# MACH.net
KiCad netlist of a schematic drawn in Altium Designer
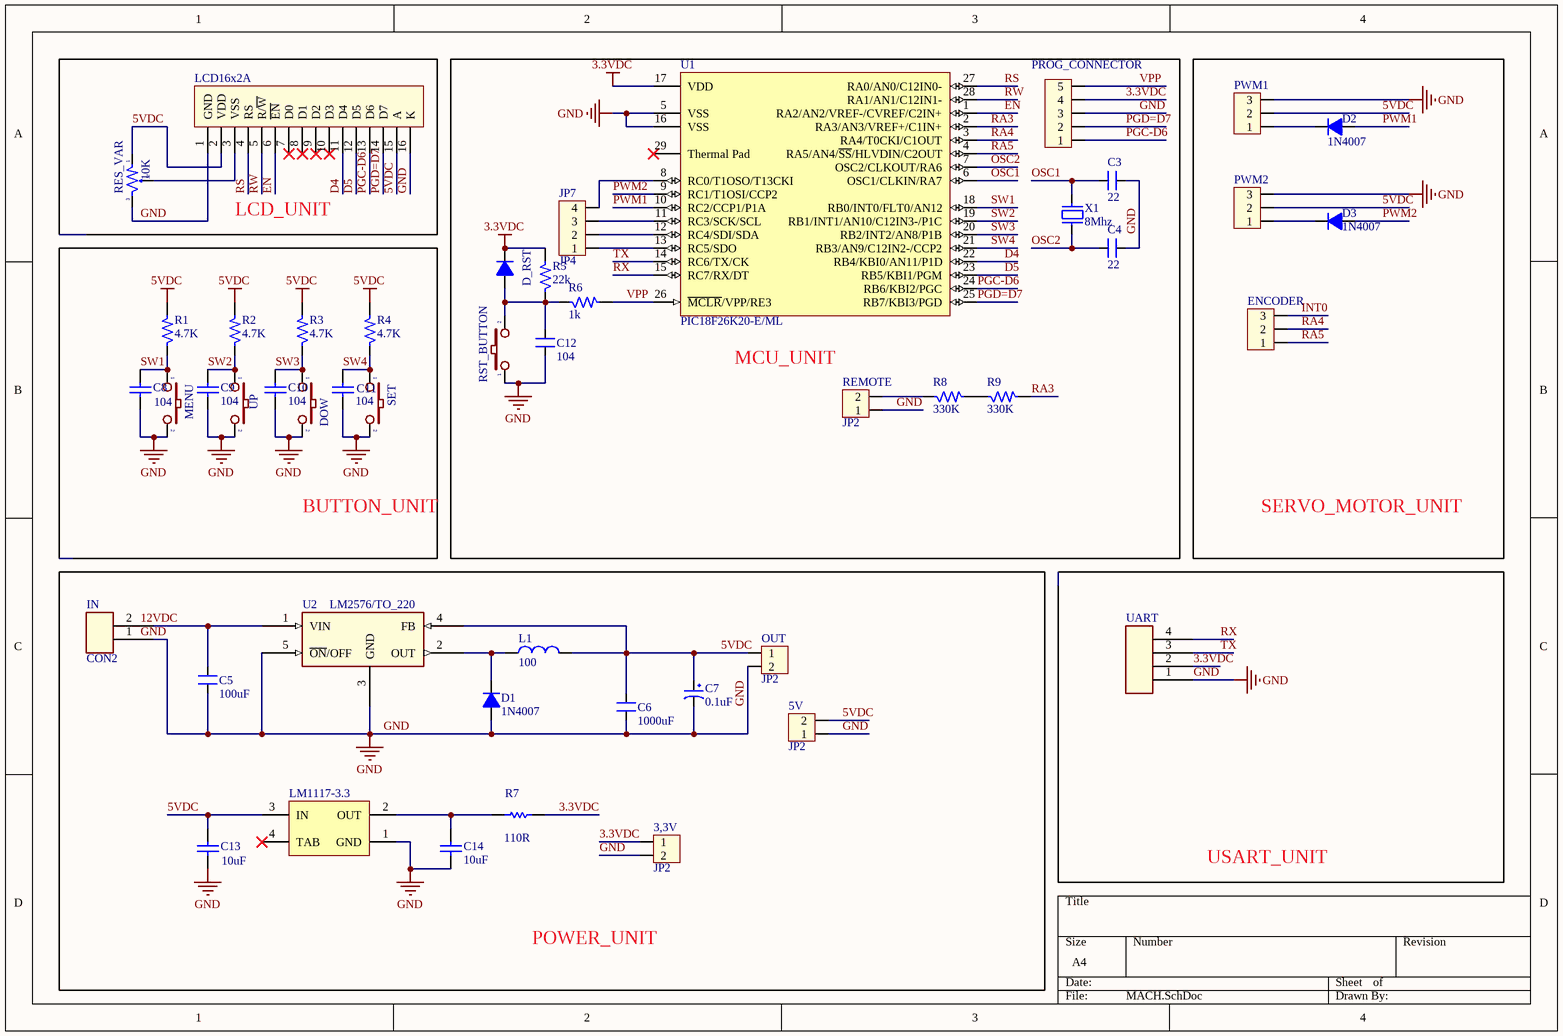
[diagram p0: MACH.SchDoc]

(export (version "E")
  (design (tool "Eeschema 10.0.6"))
  (components
    (comp (ref "3,3V")
      (value "JP2")
      (footprint "syhaunguyen:CON2")
      (description "Connector 2")
      (libsource (lib "") (part "Con2_1"))
    )
    (comp (ref "5V")
      (value "JP2")
      (footprint "syhaunguyen:CON2")
      (description "Connector 2")
      (libsource (lib "syhaunguyen") (part "Con2"))
    )
    (comp (ref "C3")
      (value "22")
      (footprint "SM-0805")
      (description "Cap SMD")
      (libsource (lib "syhaunguyen") (part "CM"))
    )
    (comp (ref "C4")
      (value "22")
      (footprint "SM-0805")
      (description "Cap SMD")
      (libsource (lib "syhaunguyen") (part "CM"))
    )
    (comp (ref "C5")
      (value "100uF")
      (footprint "CP1/2.5_SM")
      (description "Cap SMD")
      (libsource (lib "syhaunguyen") (part "CM"))
    )
    (comp (ref "C6")
      (value "1000uF")
      (footprint "CP2/4")
      (description "Cap SMD")
      (libsource (lib "syhaunguyen") (part "CM"))
    )
    (comp (ref "C7")
      (value "0.1uF")
      (footprint "CP1/2")
      (description "Cap P  0,1uF < 22uF , 16 - 50V")
      (libsource (lib "syhaunguyen") (part "CP1"))
    )
    (comp (ref "C8")
      (value "104")
      (footprint "SM-0805")
      (description "Capacitor")
      (fields (field (name "Comment") "Cap") (field (name "PUBLISHER") "Altium Limited"))
      (libsource (lib "Miscellaneous Devices") (part "Cap"))
    )
    (comp (ref "C9")
      (value "104")
      (footprint "SM-0805")
      (description "Capacitor")
      (fields (field (name "Comment") "Cap") (field (name "PUBLISHER") "Altium Limited"))
      (libsource (lib "Miscellaneous Devices") (part "Cap"))
    )
    (comp (ref "C10")
      (value "104")
      (footprint "SM-0805")
      (description "Capacitor")
      (fields (field (name "Comment") "Cap") (field (name "PUBLISHER") "Altium Limited"))
      (libsource (lib "Miscellaneous Devices") (part "Cap"))
    )
    (comp (ref "C11")
      (value "104")
      (footprint "syhaunguyen:SM-0805")
      (description "Capacitor")
      (fields (field (name "Comment") "Cap") (field (name "PUBLISHER") "Altium Limited"))
      (libsource (lib "Miscellaneous Devices") (part "Cap"))
    )
    (comp (ref "C12")
      (value "104")
      (footprint "SM-0805")
      (description "Cap SMD")
      (libsource (lib "syhaunguyen") (part "CM"))
    )
    (comp (ref "C13")
      (value "10uF")
      (footprint "CP1/2")
      (description "Capacitor")
      (fields (field (name "Comment") "Cap") (field (name "PUBLISHER") "Altium Limited"))
      (libsource (lib "Miscellaneous Devices") (part "Cap"))
    )
    (comp (ref "C14")
      (value "10uF")
      (footprint "CP1/2")
      (description "Capacitor")
      (fields (field (name "Comment") "Cap") (field (name "PUBLISHER") "Altium Limited"))
      (libsource (lib "Miscellaneous Devices") (part "Cap"))
    )
    (comp (ref "D1")
      (value "1N4007")
      (footprint "D2AN")
      (description "Diode 1A")
      (libsource (lib "syhaunguyen") (part "D1A"))
    )
    (comp (ref "D2")
      (value "1N4007")
      (footprint "D2A")
      (description "Diode 1A")
      (libsource (lib "syhaunguyen") (part "D1A"))
    )
    (comp (ref "D3")
      (value "1N4007")
      (footprint "D2A")
      (description "Diode 1A")
      (libsource (lib "syhaunguyen") (part "D1A"))
    )
    (comp (ref "DOW")
      (value "SW")
      (footprint "SW2")
      (description "Switch button 2 pin")
      (libsource (lib "syhaunguyen") (part "SW2"))
    )
    (comp (ref "D_RST")
      (value "1N5408")
      (footprint "D2A")
      (description "Diode 5A")
      (libsource (lib "syhaunguyen") (part "D5A"))
    )
    (comp (ref "ENCODER")
      (value "JP3")
      (footprint "syhaunguyen:CON3")
      (description "Connector 3")
      (libsource (lib "syhaunguyen") (part "Con3"))
    )
    (comp (ref "IN")
      (value "CON2")
      (footprint "syhaunguyen:CON2")
      (libsource (lib "NEWSYS_Library_V3") (part "CON2"))
    )
    (comp (ref "JP7")
      (value "JP4")
      (footprint "syhaunguyen:CON4")
      (description "Connector 4")
      (libsource (lib "syhaunguyen") (part "Con4"))
    )
    (comp (ref "L1")
      (value "100")
      (footprint "L/0.4")
      (description "Inductor")
      (libsource (lib "syhaunguyen") (part "L1"))
    )
    (comp (ref "LCD16x2A")
      (value "LCD")
      (footprint "LCD16X2")
      (description "LCD dipslay 16 char, 2 line")
      (libsource (lib "syhaunguyen") (part "LCD16x2"))
    )
    (comp (ref "LM1117-3.3")
      (value "LM1117MP-1.2")
      (footprint "LM1117-SOP")
      (description "800mA Low-Dropout Linear Regulator")
      (fields
        (field (name "PARTNUMBER") "LM1117MP-2.5")
        (field (name "MANUFACTURER") "National Semiconductor")
        (field (name "PUBLISHER") "Altium Limited")
      )
      (libsource (lib "NSC LDO") (part "LM1117MP-2.5"))
    )
    (comp (ref "MENU")
      (value "SW")
      (footprint "SW2")
      (description "Switch button 2 pin")
      (libsource (lib "syhaunguyen") (part "SW2"))
    )
    (comp (ref "OUT")
      (value "JP2")
      (footprint "syhaunguyen:CON2")
      (description "Connector 2")
      (libsource (lib "") (part "Con2_1"))
    )
    (comp (ref "PROG_CONNECTOR")
      (value "~")
      (footprint "CON5")
      (description "Connector 5")
      (libsource (lib "syhaunguyen") (part "Con5"))
    )
    (comp (ref "PWM1")
      (value "JP3")
      (footprint "CON3")
      (description "Connector 3")
      (libsource (lib "syhaunguyen") (part "Con3"))
    )
    (comp (ref "PWM2")
      (value "JP3")
      (footprint "CON3")
      (description "Connector 3")
      (libsource (lib "syhaunguyen") (part "Con3"))
    )
    (comp (ref "R1")
      (value "4.7K")
      (footprint "SM-0805")
      (description "Resistor 1/4W")
      (libsource (lib "syhaunguyen") (part "R"))
    )
    (comp (ref "R2")
      (value "4.7K")
      (footprint "SM-0805")
      (description "Resistor 1/4W")
      (libsource (lib "syhaunguyen") (part "R"))
    )
    (comp (ref "R3")
      (value "4.7K")
      (footprint "SM-0805")
      (description "Resistor 1/4W")
      (libsource (lib "syhaunguyen") (part "R"))
    )
    (comp (ref "R4")
      (value "4.7K")
      (footprint "SM-0805")
      (description "Resistor 1/4W")
      (libsource (lib "syhaunguyen") (part "R"))
    )
    (comp (ref "R5")
      (value "22k")
      (footprint "SM-0805")
      (description "Resistor 1/4W")
      (libsource (lib "syhaunguyen") (part "R"))
    )
    (comp (ref "R6")
      (value "1k")
      (footprint "SM-0805")
      (description "Resistor 1/4W")
      (libsource (lib "syhaunguyen") (part "R"))
    )
    (comp (ref "R7")
      (value "110R")
      (footprint "SM-0805")
      (description "Resistor")
      (fields (field (name "Comment") "Res1") (field (name "PUBLISHER") "Altium Limited"))
      (libsource (lib "Miscellaneous Devices") (part "Res1"))
    )
    (comp (ref "R8")
      (value "330K")
      (footprint "SM-1206")
      (description "Resistor 1/4W")
      (libsource (lib "syhaunguyen") (part "R"))
    )
    (comp (ref "R9")
      (value "330K")
      (footprint "SM-1206")
      (description "Resistor 1/4W")
      (libsource (lib "syhaunguyen") (part "R"))
    )
    (comp (ref "REMOTE")
      (value "JP2")
      (footprint "syhaunguyen:CON2")
      (description "Connector 2")
      (libsource (lib "syhaunguyen") (part "Con2"))
    )
    (comp (ref "RES_VAR")
      (value "10K")
      (footprint "VR")
      (description "Var Resistor")
      (libsource (lib "syhaunguyen") (part "VOL-S"))
    )
    (comp (ref "SET")
      (value "SW")
      (footprint "SW2")
      (description "Switch button 2 pin")
      (libsource (lib "syhaunguyen") (part "SW2"))
    )
    (comp (ref "SW0")
      (value "RST_BUTTON")
      (footprint "SW2")
      (description "Switch button 2 pin")
      (libsource (lib "syhaunguyen") (part "SW2"))
    )
    (comp (ref "U1")
      (value "PIC18F26K20-E/ML")
      (footprint "SOP_28M_127")
      (fields (field (name "PUBLISHER") "Altium Limited"))
      (libsource (lib "Microchip Microcontroller 8-Bit PIC18") (part "PIC18F26K20-E/ML"))
    )
    (comp (ref "U2")
      (value "LM2576/TO_220")
      (footprint "LM2576_SMD")
      (libsource (lib "NEWSYS_Library_V3") (part "LM2576/TO_220"))
    )
    (comp (ref "UART")
      (value "CON4")
      (footprint "syhaunguyen:CON4")
      (description "4-Pin Connector; pitch 2.54mm")
      (libsource (lib "NEWSYS_Library_V3") (part "CON4"))
    )
    (comp (ref "UP")
      (value "SW")
      (footprint "SW2")
      (description "Switch button 2 pin")
      (libsource (lib "syhaunguyen") (part "SW2"))
    )
    (comp (ref "X1")
      (value "8Mhz")
      (footprint "XT2")
      (description "Crystal For all Crystal 2pin.")
      (libsource (lib "syhaunguyen") (part "XT2"))
    )
  )
  (nets
    (net (code "2") (name "/D4") (class "Default")
      (node (ref "LCD16x2A") (pin "11") (pinfunction "D4_11") (pintype "passive"))
      (node (ref "U1") (pin "22") (pinfunction "RB4/KBI0/AN11/P1D_22") (pintype "bidirectional"))
    )
    (net (code "3") (name "/D5") (class "Default")
      (node (ref "LCD16x2A") (pin "12") (pinfunction "D5_12") (pintype "passive"))
      (node (ref "U1") (pin "23") (pinfunction "RB5/KBI1/PGM_23") (pintype "bidirectional"))
    )
    (net (code "4") (name "/EN") (class "Default")
      (node (ref "LCD16x2A") (pin "6") (pinfunction "~{EN}_6") (pintype "passive"))
      (node (ref "U1") (pin "1") (pinfunction "RA2/AN2/VREF-/CVREF/C2IN+_1") (pintype "bidirectional"))
    )
    (net (code "5") (name "/INT0") (class "Default")
      (node (ref "ENCODER") (pin "3") (pinfunction "3_3") (pintype "passive"))
    )
    (net (code "6") (name "/OSC1") (class "Default")
      (node (ref "C3") (pin "2") (pinfunction "2_2") (pintype "passive"))
      (node (ref "U1") (pin "6") (pinfunction "OSC1/CLKIN/RA7_6") (pintype "bidirectional"))
      (node (ref "X1") (pin "2") (pinfunction "2_2") (pintype "passive"))
    )
    (net (code "7") (name "/OSC2") (class "Default")
      (node (ref "C4") (pin "2") (pinfunction "2_2") (pintype "passive"))
      (node (ref "U1") (pin "7") (pinfunction "OSC2/CLKOUT/RA6_7") (pintype "bidirectional"))
      (node (ref "X1") (pin "1") (pinfunction "1_1") (pintype "passive"))
    )
    (net (code "8") (name "/PGC-D6") (class "Default")
      (node (ref "LCD16x2A") (pin "13") (pinfunction "D6_13") (pintype "passive"))
      (node (ref "PROG_CONNECTOR") (pin "1") (pinfunction "1_1") (pintype "passive"))
      (node (ref "U1") (pin "24") (pinfunction "RB6/KBI2/PGC_24") (pintype "bidirectional"))
    )
    (net (code "9") (name "/PGD=D7") (class "Default")
      (node (ref "LCD16x2A") (pin "14") (pinfunction "D7_14") (pintype "passive"))
      (node (ref "PROG_CONNECTOR") (pin "2") (pinfunction "2_2") (pintype "passive"))
      (node (ref "U1") (pin "25") (pinfunction "RB7/KBI3/PGD_25") (pintype "bidirectional"))
    )
    (net (code "10") (name "/PWM1") (class "Default")
      (node (ref "D2") (pin "1") (pinfunction "A_1") (pintype "passive"))
      (node (ref "U1") (pin "10") (pinfunction "RC2/CCP1/P1A_10") (pintype "bidirectional"))
    )
    (net (code "11") (name "/PWM2") (class "Default")
      (node (ref "D3") (pin "1") (pinfunction "A_1") (pintype "passive"))
      (node (ref "U1") (pin "9") (pinfunction "RC1/T1OSI/CCP2_9") (pintype "bidirectional"))
    )
    (net (code "12") (name "/RA3") (class "Default")
      (node (ref "R9") (pin "2") (pinfunction "2_2") (pintype "passive"))
      (node (ref "U1") (pin "2") (pinfunction "RA3/AN3/VREF+/C1IN+_2") (pintype "bidirectional"))
    )
    (net (code "13") (name "/RA4") (class "Default")
      (node (ref "ENCODER") (pin "2") (pinfunction "2_2") (pintype "passive"))
      (node (ref "U1") (pin "3") (pinfunction "RA4/T0CKI/C1OUT_3") (pintype "bidirectional"))
    )
    (net (code "14") (name "/RA5") (class "Default")
      (node (ref "ENCODER") (pin "1") (pinfunction "1_1") (pintype "passive"))
      (node (ref "U1") (pin "4") (pinfunction "RA5/AN4/~{SS}/HLVDIN/C2OUT_4") (pintype "bidirectional"))
    )
    (net (code "15") (name "/RS") (class "Default")
      (node (ref "LCD16x2A") (pin "4") (pinfunction "RS_4") (pintype "passive"))
      (node (ref "U1") (pin "27") (pinfunction "RA0/AN0/C12IN0-_27") (pintype "bidirectional"))
    )
    (net (code "16") (name "/RW") (class "Default")
      (node (ref "LCD16x2A") (pin "5") (pinfunction "R/~{W}_5") (pintype "passive"))
      (node (ref "U1") (pin "28") (pinfunction "RA1/AN1/C12IN1-_28") (pintype "bidirectional"))
    )
    (net (code "17") (name "/RX") (class "Default")
      (node (ref "U1") (pin "15") (pinfunction "RC7/RX/DT_15") (pintype "bidirectional"))
      (node (ref "UART") (pin "4") (pinfunction "4_4") (pintype "passive"))
    )
    (net (code "18") (name "/SW1") (class "Default")
      (node (ref "C8") (pin "2") (pinfunction "2_2") (pintype "passive"))
      (node (ref "MENU") (pin "1") (pinfunction "1_1") (pintype "passive"))
      (node (ref "R1") (pin "1") (pinfunction "1_1") (pintype "passive"))
      (node (ref "U1") (pin "18") (pinfunction "RB0/INT0/FLT0/AN12_18") (pintype "bidirectional"))
    )
    (net (code "19") (name "/SW2") (class "Default")
      (node (ref "C9") (pin "2") (pinfunction "2_2") (pintype "passive"))
      (node (ref "R2") (pin "1") (pinfunction "1_1") (pintype "passive"))
      (node (ref "U1") (pin "19") (pinfunction "RB1/INT1/AN10/C12IN3-/P1C_19") (pintype "bidirectional"))
      (node (ref "UP") (pin "1") (pinfunction "1_1") (pintype "passive"))
    )
    (net (code "20") (name "/SW3") (class "Default")
      (node (ref "C10") (pin "2") (pinfunction "2_2") (pintype "passive"))
      (node (ref "DOW") (pin "1") (pinfunction "1_1") (pintype "passive"))
      (node (ref "R3") (pin "1") (pinfunction "1_1") (pintype "passive"))
      (node (ref "U1") (pin "20") (pinfunction "RB2/INT2/AN8/P1B_20") (pintype "bidirectional"))
    )
    (net (code "21") (name "/SW4") (class "Default")
      (node (ref "C11") (pin "2") (pinfunction "2_2") (pintype "passive"))
      (node (ref "R4") (pin "1") (pinfunction "1_1") (pintype "passive"))
      (node (ref "SET") (pin "1") (pinfunction "1_1") (pintype "passive"))
      (node (ref "U1") (pin "21") (pinfunction "RB3/AN9/C12IN2-/CCP2_21") (pintype "bidirectional"))
    )
    (net (code "22") (name "/TX") (class "Default")
      (node (ref "U1") (pin "14") (pinfunction "RC6/TX/CK_14") (pintype "bidirectional"))
      (node (ref "UART") (pin "3") (pinfunction "3_3") (pintype "passive"))
    )
    (net (code "23") (name "/VPP") (class "Default")
      (node (ref "PROG_CONNECTOR") (pin "5") (pinfunction "5_5") (pintype "passive"))
      (node (ref "R6") (pin "2") (pinfunction "2_2") (pintype "passive"))
      (node (ref "U1") (pin "26") (pinfunction "~{MCLR}/VPP/RE3_26") (pintype "input"))
    )
    (net (code "24") (name "3.3VDC") (class "Default")
      (node (ref "3,3V") (pin "1") (pinfunction "1_1") (pintype "passive"))
      (node (ref "D_RST") (pin "2") (pinfunction "K_2") (pintype "passive"))
      (node (ref "PROG_CONNECTOR") (pin "4") (pinfunction "4_4") (pintype "passive"))
      (node (ref "R5") (pin "2") (pinfunction "2_2") (pintype "passive"))
      (node (ref "R7") (pin "2") (pinfunction "2_2") (pintype "passive"))
      (node (ref "U1") (pin "17") (pinfunction "VDD_17") (pintype "power_in"))
      (node (ref "UART") (pin "2") (pinfunction "2_2") (pintype "passive"))
    )
    (net (code "25") (name "5VDC") (class "Default")
      (node (ref "5V") (pin "2") (pinfunction "2_2") (pintype "passive"))
      (node (ref "C13") (pin "2") (pinfunction "2_2") (pintype "passive"))
      (node (ref "C6") (pin "2") (pinfunction "2_2") (pintype "passive"))
      (node (ref "C7") (pin "1") (pinfunction "1_1") (pintype "passive"))
      (node (ref "L1") (pin "2") (pinfunction "2_2") (pintype "passive"))
      (node (ref "LCD16x2A") (pin "15") (pinfunction "A_15") (pintype "passive"))
      (node (ref "LCD16x2A") (pin "2") (pinfunction "VDD_2") (pintype "passive"))
      (node (ref "LM1117-3.3") (pin "3") (pinfunction "IN_3") (pintype "power_in"))
      (node (ref "OUT") (pin "1") (pinfunction "1_1") (pintype "passive"))
      (node (ref "PWM1") (pin "2") (pinfunction "2_2") (pintype "passive"))
      (node (ref "PWM2") (pin "2") (pinfunction "2_2") (pintype "passive"))
      (node (ref "R1") (pin "2") (pinfunction "2_2") (pintype "passive"))
      (node (ref "R2") (pin "2") (pinfunction "2_2") (pintype "passive"))
      (node (ref "R3") (pin "2") (pinfunction "2_2") (pintype "passive"))
      (node (ref "R4") (pin "2") (pinfunction "2_2") (pintype "passive"))
      (node (ref "RES_VAR") (pin "1") (pinfunction "1_1") (pintype "passive"))
      (node (ref "U2") (pin "4") (pinfunction "FB_4") (pintype "input"))
    )
    (net (code "26") (name "GND") (class "Default")
      (node (ref "3,3V") (pin "2") (pinfunction "2_2") (pintype "passive"))
      (node (ref "5V") (pin "1") (pinfunction "1_1") (pintype "passive"))
      (node (ref "C10") (pin "1") (pinfunction "1_1") (pintype "passive"))
      (node (ref "C11") (pin "1") (pinfunction "1_1") (pintype "passive"))
      (node (ref "C12") (pin "1") (pinfunction "1_1") (pintype "passive"))
      (node (ref "C13") (pin "1") (pinfunction "1_1") (pintype "passive"))
      (node (ref "C14") (pin "1") (pinfunction "1_1") (pintype "passive"))
      (node (ref "C3") (pin "1") (pinfunction "1_1") (pintype "passive"))
      (node (ref "C4") (pin "1") (pinfunction "1_1") (pintype "passive"))
      (node (ref "C5") (pin "1") (pinfunction "1_1") (pintype "passive"))
      (node (ref "C6") (pin "1") (pinfunction "1_1") (pintype "passive"))
      (node (ref "C7") (pin "2") (pinfunction "2_2") (pintype "passive"))
      (node (ref "C8") (pin "1") (pinfunction "1_1") (pintype "passive"))
      (node (ref "C9") (pin "1") (pinfunction "1_1") (pintype "passive"))
      (node (ref "D1") (pin "1") (pinfunction "A_1") (pintype "passive"))
      (node (ref "DOW") (pin "2") (pinfunction "2_2") (pintype "passive"))
      (node (ref "IN") (pin "1") (pintype "passive"))
      (node (ref "LCD16x2A") (pin "1") (pinfunction "GND_1") (pintype "passive"))
      (node (ref "LCD16x2A") (pin "16") (pinfunction "K_16") (pintype "passive"))
      (node (ref "LM1117-3.3") (pin "1") (pinfunction "GND_1") (pintype "power_in"))
      (node (ref "MENU") (pin "2") (pinfunction "2_2") (pintype "passive"))
      (node (ref "OUT") (pin "2") (pinfunction "2_2") (pintype "passive"))
      (node (ref "PROG_CONNECTOR") (pin "3") (pinfunction "3_3") (pintype "passive"))
      (node (ref "PWM1") (pin "3") (pinfunction "3_3") (pintype "passive"))
      (node (ref "PWM2") (pin "3") (pinfunction "3_3") (pintype "passive"))
      (node (ref "REMOTE") (pin "1") (pinfunction "1_1") (pintype "passive"))
      (node (ref "RES_VAR") (pin "3") (pinfunction "3_3") (pintype "passive"))
      (node (ref "SET") (pin "2") (pinfunction "2_2") (pintype "passive"))
      (node (ref "SW0") (pin "1") (pinfunction "1_1") (pintype "passive"))
      (node (ref "U1") (pin "16") (pinfunction "VSS_16") (pintype "power_in"))
      (node (ref "U1") (pin "5") (pinfunction "VSS_5") (pintype "power_in"))
      (node (ref "U2") (pin "3") (pinfunction "GND_3") (pintype "passive"))
      (node (ref "U2") (pin "5") (pinfunction "~{ON}/OFF_5") (pintype "input"))
      (node (ref "UART") (pin "1") (pinfunction "1_1") (pintype "passive"))
      (node (ref "UP") (pin "2") (pinfunction "2_2") (pintype "passive"))
    )
    (net (code "27") (name "Net-(D1-K)") (class "Default")
      (node (ref "D1") (pin "2") (pinfunction "K_2") (pintype "passive"))
      (node (ref "L1") (pin "1") (pinfunction "1_1") (pintype "passive"))
      (node (ref "U2") (pin "2") (pinfunction "OUT_2") (pintype "output"))
    )
    (net (code "28") (name "Net-(D2-K)") (class "Default")
      (node (ref "D2") (pin "2") (pinfunction "K_2") (pintype "passive"))
      (node (ref "PWM1") (pin "1") (pinfunction "1_1") (pintype "passive"))
    )
    (net (code "29") (name "Net-(D3-K)") (class "Default")
      (node (ref "D3") (pin "2") (pinfunction "K_2") (pintype "passive"))
      (node (ref "PWM2") (pin "1") (pinfunction "1_1") (pintype "passive"))
    )
    (net (code "30") (name "Net-(D_RST-A)") (class "Default")
      (node (ref "C12") (pin "2") (pinfunction "2_2") (pintype "passive"))
      (node (ref "D_RST") (pin "1") (pinfunction "A_1") (pintype "passive"))
      (node (ref "R5") (pin "1") (pinfunction "1_1") (pintype "passive"))
      (node (ref "R6") (pin "1") (pinfunction "1_1") (pintype "passive"))
      (node (ref "SW0") (pin "2") (pinfunction "2_2") (pintype "passive"))
    )
    (net (code "31") (name "Net-(LCD16x2A-VSS)") (class "Default")
      (node (ref "LCD16x2A") (pin "3") (pinfunction "VSS_3") (pintype "passive"))
      (node (ref "RES_VAR") (pin "2") (pinfunction "2_2") (pintype "passive"))
    )
    (net (code "32") (name "Net-(LM1117-3.3-OUT)") (class "Default")
      (node (ref "C14") (pin "2") (pinfunction "2_2") (pintype "passive"))
      (node (ref "LM1117-3.3") (pin "2") (pinfunction "OUT_2") (pintype "power_in"))
      (node (ref "R7") (pin "1") (pinfunction "1_1") (pintype "passive"))
    )
    (net (code "33") (name "Net-(R8-Pad1)") (class "Default")
      (node (ref "R8") (pin "1") (pinfunction "1_1") (pintype "passive"))
      (node (ref "REMOTE") (pin "2") (pinfunction "2_2") (pintype "passive"))
    )
    (net (code "34") (name "Net-(R8-Pad2)") (class "Default")
      (node (ref "R8") (pin "2") (pinfunction "2_2") (pintype "passive"))
      (node (ref "R9") (pin "1") (pinfunction "1_1") (pintype "passive"))
    )
    (net (code "35") (name "Net-(U1-RC0{slash}T1OSO{slash}T13CKI)") (class "Default")
      (node (ref "JP7") (pin "4") (pinfunction "4_4") (pintype "passive"))
      (node (ref "U1") (pin "8") (pinfunction "RC0/T1OSO/T13CKI_8") (pintype "bidirectional"))
    )
    (net (code "36") (name "Net-(U1-RC3{slash}SCK{slash}SCL)") (class "Default")
      (node (ref "JP7") (pin "3") (pinfunction "3_3") (pintype "passive"))
      (node (ref "U1") (pin "11") (pinfunction "RC3/SCK/SCL_11") (pintype "bidirectional"))
    )
    (net (code "37") (name "Net-(U1-RC4{slash}SDI{slash}SDA)") (class "Default")
      (node (ref "JP7") (pin "2") (pinfunction "2_2") (pintype "passive"))
      (node (ref "U1") (pin "12") (pinfunction "RC4/SDI/SDA_12") (pintype "bidirectional"))
    )
    (net (code "38") (name "Net-(U1-RC5{slash}SDO)") (class "Default")
      (node (ref "JP7") (pin "1") (pinfunction "1_1") (pintype "passive"))
      (node (ref "U1") (pin "13") (pinfunction "RC5/SDO_13") (pintype "bidirectional"))
    )
    (net (code "39") (name "Net-(U2-VIN)") (class "Default")
      (node (ref "C5") (pin "2") (pinfunction "2_2") (pintype "passive"))
      (node (ref "IN") (pin "2") (pintype "passive"))
      (node (ref "U2") (pin "1") (pinfunction "VIN_1") (pintype "input"))
    )
    (net (code "40") (name "unconnected-(LCD16x2A-D0-Pad7)") (class "Default")
      (node (ref "LCD16x2A") (pin "7") (pinfunction "D0_7") (pintype "passive+no_connect"))
    )
    (net (code "41") (name "unconnected-(LCD16x2A-D1-Pad8)") (class "Default")
      (node (ref "LCD16x2A") (pin "8") (pinfunction "D1_8") (pintype "passive+no_connect"))
    )
    (net (code "42") (name "unconnected-(LCD16x2A-D2-Pad9)") (class "Default")
      (node (ref "LCD16x2A") (pin "9") (pinfunction "D2_9") (pintype "passive+no_connect"))
    )
    (net (code "43") (name "unconnected-(LCD16x2A-D3-Pad10)") (class "Default")
      (node (ref "LCD16x2A") (pin "10") (pinfunction "D3_10") (pintype "passive+no_connect"))
    )
    (net (code "44") (name "unconnected-(LM1117-3.3-TAB-Pad4)") (class "Default")
      (node (ref "LM1117-3.3") (pin "4") (pinfunction "TAB_4") (pintype "power_in+no_connect"))
    )
    (net (code "45") (name "unconnected-(U1-Thermal_Pad-Pad29)") (class "Default")
      (node (ref "U1") (pin "29") (pinfunction "Thermal_Pad_29") (pintype "power_in+no_connect"))
    )
  )
)
